# USB_Power.net
KiCad netlist of a schematic drawn in Altium Designer
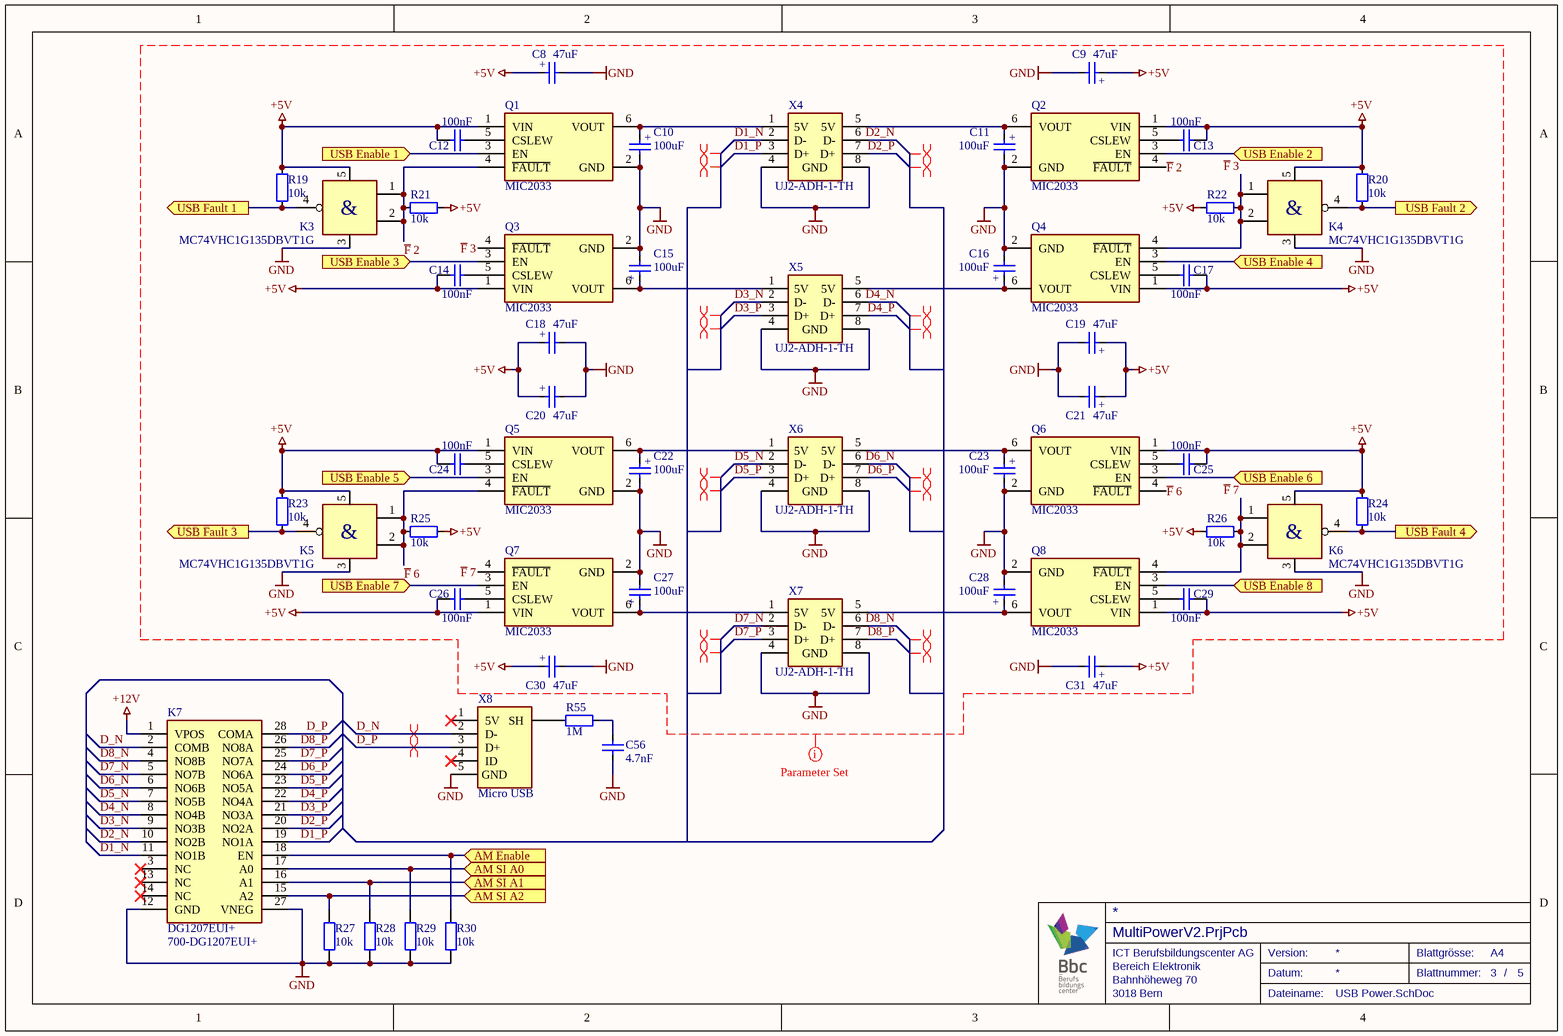
[diagram p0: USB Power.SchDoc]

(export (version "E")
  (design (tool "Eeschema 10.0.6"))
  (components
    (comp (ref "C8")
      (value "47uF")
      (footprint "T58W9476M6R3C0300")
      (description "Polarized Capacitor")
      (fields (field (name "Comment") "Capacitor P") (field (name "PUBLISHER") "ICT Berufsbildungscenter AG"))
      (libsource (lib "SchematicLibrary") (part "Capacitor P"))
    )
    (comp (ref "C9")
      (value "47uF")
      (footprint "T58W9476M6R3C0300")
      (description "Polarized Capacitor")
      (fields (field (name "Comment") "Capacitor P") (field (name "PUBLISHER") "ICT Berufsbildungscenter AG"))
      (libsource (lib "SchematicLibrary") (part "Capacitor P"))
    )
    (comp (ref "C10")
      (value "100uF")
      (footprint "CAP TAN A H")
      (description "Polarized Capacitor")
      (fields (field (name "Comment") "Capacitor P") (field (name "PUBLISHER") "ICT Berufsbildungscenter AG"))
      (libsource (lib "SchematicLibrary") (part "Capacitor P"))
    )
    (comp (ref "C11")
      (value "100uF")
      (footprint "CAP TAN A H")
      (description "Polarized Capacitor")
      (fields (field (name "Comment") "Capacitor P") (field (name "PUBLISHER") "ICT Berufsbildungscenter AG"))
      (libsource (lib "SchematicLibrary") (part "Capacitor P"))
    )
    (comp (ref "C12")
      (value "100nF")
      (footprint "CAP CER 0805 R")
      (description "Non polarized capacitor")
      (fields (field (name "Comment") "Capacitor") (field (name "PUBLISHER") "ICT Berufsbildungscenter AG"))
      (libsource (lib "BBC_Components") (part "Capacitor"))
    )
    (comp (ref "C13")
      (value "100nF")
      (footprint "CAP CER 0805 R")
      (description "Non polarized capacitor")
      (fields (field (name "Comment") "Capacitor") (field (name "PUBLISHER") "ICT Berufsbildungscenter AG"))
      (libsource (lib "BBC_Components") (part "Capacitor"))
    )
    (comp (ref "C14")
      (value "100nF")
      (footprint "CAP CER 0805 R")
      (description "Non polarized capacitor")
      (fields (field (name "Comment") "Capacitor") (field (name "PUBLISHER") "ICT Berufsbildungscenter AG"))
      (libsource (lib "BBC_Components") (part "Capacitor"))
    )
    (comp (ref "C15")
      (value "100uF")
      (footprint "CAP TAN A H")
      (description "Polarized Capacitor")
      (fields (field (name "Comment") "Capacitor P") (field (name "PUBLISHER") "ICT Berufsbildungscenter AG"))
      (libsource (lib "SchematicLibrary") (part "Capacitor P"))
    )
    (comp (ref "C16")
      (value "100uF")
      (footprint "CAP TAN A H")
      (description "Polarized Capacitor")
      (fields (field (name "Comment") "Capacitor P") (field (name "PUBLISHER") "ICT Berufsbildungscenter AG"))
      (libsource (lib "SchematicLibrary") (part "Capacitor P"))
    )
    (comp (ref "C17")
      (value "100nF")
      (footprint "CAP CER 0805 R")
      (description "Non polarized capacitor")
      (fields (field (name "Comment") "Capacitor") (field (name "PUBLISHER") "ICT Berufsbildungscenter AG"))
      (libsource (lib "BBC_Components") (part "Capacitor"))
    )
    (comp (ref "C18")
      (value "47uF")
      (footprint "T58W9476M6R3C0300")
      (description "Polarized Capacitor")
      (fields (field (name "Comment") "Capacitor P") (field (name "PUBLISHER") "ICT Berufsbildungscenter AG"))
      (libsource (lib "SchematicLibrary") (part "Capacitor P"))
    )
    (comp (ref "C19")
      (value "47uF")
      (footprint "T58W9476M6R3C0300")
      (description "Polarized Capacitor")
      (fields (field (name "Comment") "Capacitor P") (field (name "PUBLISHER") "ICT Berufsbildungscenter AG"))
      (libsource (lib "SchematicLibrary") (part "Capacitor P"))
    )
    (comp (ref "C20")
      (value "47uF")
      (footprint "T58W9476M6R3C0300")
      (description "Polarized Capacitor")
      (fields (field (name "Comment") "Capacitor P") (field (name "PUBLISHER") "ICT Berufsbildungscenter AG"))
      (libsource (lib "SchematicLibrary") (part "Capacitor P"))
    )
    (comp (ref "C21")
      (value "47uF")
      (footprint "T58W9476M6R3C0300")
      (description "Polarized Capacitor")
      (fields (field (name "Comment") "Capacitor P") (field (name "PUBLISHER") "ICT Berufsbildungscenter AG"))
      (libsource (lib "SchematicLibrary") (part "Capacitor P"))
    )
    (comp (ref "C22")
      (value "100uF")
      (footprint "CAP TAN A H")
      (description "Polarized Capacitor")
      (fields (field (name "Comment") "Capacitor P") (field (name "PUBLISHER") "ICT Berufsbildungscenter AG"))
      (libsource (lib "SchematicLibrary") (part "Capacitor P"))
    )
    (comp (ref "C23")
      (value "100uF")
      (footprint "CAP TAN A H")
      (description "Polarized Capacitor")
      (fields (field (name "Comment") "Capacitor P") (field (name "PUBLISHER") "ICT Berufsbildungscenter AG"))
      (libsource (lib "SchematicLibrary") (part "Capacitor P"))
    )
    (comp (ref "C24")
      (value "100nF")
      (footprint "CAP CER 0805 R")
      (description "Non polarized capacitor")
      (fields (field (name "Comment") "Capacitor") (field (name "PUBLISHER") "ICT Berufsbildungscenter AG"))
      (libsource (lib "BBC_Components") (part "Capacitor"))
    )
    (comp (ref "C25")
      (value "100nF")
      (footprint "CAP CER 0805 R")
      (description "Non polarized capacitor")
      (fields (field (name "Comment") "Capacitor") (field (name "PUBLISHER") "ICT Berufsbildungscenter AG"))
      (libsource (lib "BBC_Components") (part "Capacitor"))
    )
    (comp (ref "C26")
      (value "100nF")
      (footprint "CAP CER 0805 R")
      (description "Non polarized capacitor")
      (fields (field (name "Comment") "Capacitor") (field (name "PUBLISHER") "ICT Berufsbildungscenter AG"))
      (libsource (lib "BBC_Components") (part "Capacitor"))
    )
    (comp (ref "C27")
      (value "100uF")
      (footprint "CAP TAN A H")
      (description "Polarized Capacitor")
      (fields (field (name "Comment") "Capacitor P") (field (name "PUBLISHER") "ICT Berufsbildungscenter AG"))
      (libsource (lib "SchematicLibrary") (part "Capacitor P"))
    )
    (comp (ref "C28")
      (value "100uF")
      (footprint "CAP TAN A H")
      (description "Polarized Capacitor")
      (fields (field (name "Comment") "Capacitor P") (field (name "PUBLISHER") "ICT Berufsbildungscenter AG"))
      (libsource (lib "SchematicLibrary") (part "Capacitor P"))
    )
    (comp (ref "C29")
      (value "100nF")
      (footprint "CAP CER 0805 R")
      (description "Non polarized capacitor")
      (fields (field (name "Comment") "Capacitor") (field (name "PUBLISHER") "ICT Berufsbildungscenter AG"))
      (libsource (lib "BBC_Components") (part "Capacitor"))
    )
    (comp (ref "C30")
      (value "47uF")
      (footprint "T58W9476M6R3C0300")
      (description "Polarized Capacitor")
      (fields (field (name "Comment") "Capacitor P") (field (name "PUBLISHER") "ICT Berufsbildungscenter AG"))
      (libsource (lib "SchematicLibrary") (part "Capacitor P"))
    )
    (comp (ref "C31")
      (value "47uF")
      (footprint "T58W9476M6R3C0300")
      (description "Polarized Capacitor")
      (fields (field (name "Comment") "Capacitor P") (field (name "PUBLISHER") "ICT Berufsbildungscenter AG"))
      (libsource (lib "SchematicLibrary") (part "Capacitor P"))
    )
    (comp (ref "C56")
      (value "4.7nF")
      (footprint "CAP CER 0805 R")
      (description "Non polarized capacitor")
      (fields (field (name "Comment") "Capacitor") (field (name "PUBLISHER") "ICT Berufsbildungscenter AG"))
      (libsource (lib "SchematicLibrary") (part "Capacitor"))
    )
    (comp (ref "K3")
      (value "MC74VHC1G135DBVT1G")
      (footprint "SOT95P275X110-5N")
      (libsource (lib "") (part "MC74VHC1G135DBVT1G_1"))
    )
    (comp (ref "K4")
      (value "MC74VHC1G135DBVT1G")
      (footprint "SOT95P275X110-5N")
      (libsource (lib "SchematicLibrary") (part "MC74VHC1G135DBVT1G"))
    )
    (comp (ref "K5")
      (value "MC74VHC1G135DBVT1G")
      (footprint "SOT95P275X110-5N")
      (libsource (lib "") (part "MC74VHC1G135DBVT1G_1"))
    )
    (comp (ref "K6")
      (value "MC74VHC1G135DBVT1G")
      (footprint "SOT95P275X110-5N")
      (libsource (lib "SchematicLibrary") (part "MC74VHC1G135DBVT1G"))
    )
    (comp (ref "K7")
      (value "DG1207EUI+")
      (footprint "TSOP65P640X100-28N")
      (description "Analog Switch ICs")
      (fields
        (field (name "MOUSER PART NUMBER") "700-DG1207EUI+")
        (field (name "SUPPLIER PART NUMBER 1") "700-DG1207EUI+")
      )
      (libsource (lib "SchematicLibrary") (part "DG1207EUI+"))
    )
    (comp (ref "Q1")
      (value "MIC2033")
      (footprint "SOT-23-6L")
      (libsource (lib "SchematicLibrary") (part "MIC2033"))
    )
    (comp (ref "Q2") (value "MIC2033") (footprint "SOT-23-6L") (libsource (lib "") (part "MIC2033_3")))
    (comp (ref "Q3") (value "MIC2033") (footprint "SOT-23-6L") (libsource (lib "") (part "MIC2033_1")))
    (comp (ref "Q4") (value "MIC2033") (footprint "SOT-23-6L") (libsource (lib "") (part "MIC2033_2")))
    (comp (ref "Q5")
      (value "MIC2033")
      (footprint "SOT-23-6L")
      (libsource (lib "SchematicLibrary") (part "MIC2033"))
    )
    (comp (ref "Q6") (value "MIC2033") (footprint "SOT-23-6L") (libsource (lib "") (part "MIC2033_3")))
    (comp (ref "Q7") (value "MIC2033") (footprint "SOT-23-6L") (libsource (lib "") (part "MIC2033_1")))
    (comp (ref "Q8") (value "MIC2033") (footprint "SOT-23-6L") (libsource (lib "") (part "MIC2033_2")))
    (comp (ref "R19")
      (value "10k")
      (footprint "RES 0805 R")
      (description "Resistor")
      (fields (field (name "PUBLISHER") "ICT Berufsbildungscenter AG"))
      (libsource (lib "SchematicLibrary") (part "Resistor"))
    )
    (comp (ref "R20")
      (value "10k")
      (footprint "RES 0805 R")
      (description "Resistor")
      (fields (field (name "PUBLISHER") "ICT Berufsbildungscenter AG"))
      (libsource (lib "") (part "Resistor_2"))
    )
    (comp (ref "R21")
      (value "10k")
      (footprint "RES 0805 R")
      (description "Resistor")
      (fields (field (name "PUBLISHER") "ICT Berufsbildungscenter AG"))
      (libsource (lib "") (part "Resistor_2"))
    )
    (comp (ref "R22")
      (value "10k")
      (footprint "RES 0805 R")
      (description "Resistor")
      (fields (field (name "PUBLISHER") "ICT Berufsbildungscenter AG"))
      (libsource (lib "") (part "Resistor_1"))
    )
    (comp (ref "R23")
      (value "10k")
      (footprint "RES 0805 R")
      (description "Resistor")
      (fields (field (name "PUBLISHER") "ICT Berufsbildungscenter AG"))
      (libsource (lib "SchematicLibrary") (part "Resistor"))
    )
    (comp (ref "R24")
      (value "10k")
      (footprint "RES 0805 R")
      (description "Resistor")
      (fields (field (name "PUBLISHER") "ICT Berufsbildungscenter AG"))
      (libsource (lib "") (part "Resistor_2"))
    )
    (comp (ref "R25")
      (value "10k")
      (footprint "RES 0805 R")
      (description "Resistor")
      (fields (field (name "PUBLISHER") "ICT Berufsbildungscenter AG"))
      (libsource (lib "") (part "Resistor_2"))
    )
    (comp (ref "R26")
      (value "10k")
      (footprint "RES 0805 R")
      (description "Resistor")
      (fields (field (name "PUBLISHER") "ICT Berufsbildungscenter AG"))
      (libsource (lib "") (part "Resistor_1"))
    )
    (comp (ref "R27")
      (value "10k")
      (footprint "RES 0805 R")
      (description "Resistor")
      (fields (field (name "PUBLISHER") "ICT Berufsbildungscenter AG"))
      (libsource (lib "BBC_Components") (part "Resistor"))
    )
    (comp (ref "R28")
      (value "10k")
      (footprint "RES 0805 R")
      (description "Resistor")
      (fields (field (name "PUBLISHER") "ICT Berufsbildungscenter AG"))
      (libsource (lib "BBC_Components") (part "Resistor"))
    )
    (comp (ref "R29")
      (value "10k")
      (footprint "RES 0805 R")
      (description "Resistor")
      (fields (field (name "PUBLISHER") "ICT Berufsbildungscenter AG"))
      (libsource (lib "BBC_Components") (part "Resistor"))
    )
    (comp (ref "R30")
      (value "10k")
      (footprint "RES 0805 R")
      (description "Resistor")
      (fields (field (name "PUBLISHER") "ICT Berufsbildungscenter AG"))
      (libsource (lib "BBC_Components") (part "Resistor"))
    )
    (comp (ref "R55")
      (value "1M")
      (footprint "RES 0805 R")
      (description "Resistor")
      (fields (field (name "PUBLISHER") "ICT Berufsbildungscenter AG"))
      (libsource (lib "") (part "Resistor_2"))
    )
    (comp (ref "X4")
      (value "UJ2-ADH-1-TH")
      (footprint "SamacSys:UJ2-ADH-1-TH")
      (description "USB Type A")
      (fields (field (name "MOUSER PART NUMBER") "490-UJ2-ADH-1-TH"))
      (libsource (lib "SchematicLibrary") (part "UJ2-ADH-1-TH"))
    )
    (comp (ref "X5")
      (value "UJ2-ADH-1-TH")
      (footprint "UJ2-ADH-1-TH")
      (description "USB Type A")
      (fields (field (name "MOUSER PART NUMBER") "490-UJ2-ADH-1-TH"))
      (libsource (lib "SchematicLibrary") (part "UJ2-ADH-1-TH"))
    )
    (comp (ref "X6")
      (value "UJ2-ADH-1-TH")
      (footprint "UJ2-ADH-1-TH")
      (description "USB Type A")
      (fields (field (name "MOUSER PART NUMBER") "490-UJ2-ADH-1-TH"))
      (libsource (lib "SchematicLibrary") (part "UJ2-ADH-1-TH"))
    )
    (comp (ref "X7")
      (value "UJ2-ADH-1-TH")
      (footprint "SamacSys:UJ2-ADH-1-TH")
      (description "USB Type A")
      (fields (field (name "MOUSER PART NUMBER") "490-UJ2-ADH-1-TH"))
      (libsource (lib "SchematicLibrary") (part "UJ2-ADH-1-TH"))
    )
    (comp (ref "X8")
      (value "Micro USB")
      (footprint "UJ2-MIBH-4-SMT-TR")
      (description "board to board header")
      (fields (field (name "PUBLISHER") "ICT Berufsbildungscenter AG"))
      (libsource (lib "SchematicLibrary") (part "Micro USB"))
    )
  )
  (nets
    (net (code "1") (name "+5V") (class "Default")
      (node (ref "C12") (pin "1") (pinfunction "1_1") (pintype "passive"))
      (node (ref "C13") (pin "1") (pinfunction "1_1") (pintype "passive"))
      (node (ref "C14") (pin "1") (pinfunction "1_1") (pintype "passive"))
      (node (ref "C17") (pin "1") (pinfunction "1_1") (pintype "passive"))
      (node (ref "C18") (pin "A") (pinfunction "Anode_A") (pintype "passive"))
      (node (ref "C19") (pin "A") (pinfunction "Anode_A") (pintype "passive"))
      (node (ref "C20") (pin "A") (pinfunction "Anode_A") (pintype "passive"))
      (node (ref "C21") (pin "A") (pinfunction "Anode_A") (pintype "passive"))
      (node (ref "C24") (pin "1") (pinfunction "1_1") (pintype "passive"))
      (node (ref "C25") (pin "1") (pinfunction "1_1") (pintype "passive"))
      (node (ref "C26") (pin "1") (pinfunction "1_1") (pintype "passive"))
      (node (ref "C29") (pin "1") (pinfunction "1_1") (pintype "passive"))
      (node (ref "C30") (pin "A") (pinfunction "Anode_A") (pintype "passive"))
      (node (ref "C31") (pin "A") (pinfunction "Anode_A") (pintype "passive"))
      (node (ref "C8") (pin "A") (pinfunction "Anode_A") (pintype "passive"))
      (node (ref "C9") (pin "A") (pinfunction "Anode_A") (pintype "passive"))
      (node (ref "K3") (pin "5") (pinfunction "VCC_5") (pintype "passive"))
      (node (ref "K4") (pin "5") (pinfunction "VCC_5") (pintype "passive"))
      (node (ref "K5") (pin "5") (pinfunction "VCC_5") (pintype "passive"))
      (node (ref "K6") (pin "5") (pinfunction "VCC_5") (pintype "passive"))
      (node (ref "Q1") (pin "1") (pinfunction "VIN_1") (pintype "passive"))
      (node (ref "Q2") (pin "1") (pinfunction "VIN_1") (pintype "passive"))
      (node (ref "Q3") (pin "1") (pinfunction "VIN_1") (pintype "passive"))
      (node (ref "Q4") (pin "1") (pinfunction "VIN_1") (pintype "passive"))
      (node (ref "Q5") (pin "1") (pinfunction "VIN_1") (pintype "passive"))
      (node (ref "Q6") (pin "1") (pinfunction "VIN_1") (pintype "passive"))
      (node (ref "Q7") (pin "1") (pinfunction "VIN_1") (pintype "passive"))
      (node (ref "Q8") (pin "1") (pinfunction "VIN_1") (pintype "passive"))
      (node (ref "R19") (pin "1") (pinfunction "1_1") (pintype "passive"))
      (node (ref "R20") (pin "1") (pinfunction "1_1") (pintype "passive"))
      (node (ref "R21") (pin "1") (pinfunction "1_1") (pintype "passive"))
      (node (ref "R22") (pin "1") (pinfunction "1_1") (pintype "passive"))
      (node (ref "R23") (pin "1") (pinfunction "1_1") (pintype "passive"))
      (node (ref "R24") (pin "1") (pinfunction "1_1") (pintype "passive"))
      (node (ref "R25") (pin "1") (pinfunction "1_1") (pintype "passive"))
      (node (ref "R26") (pin "1") (pinfunction "1_1") (pintype "passive"))
    )
    (net (code "2") (name "+12V") (class "Default")
      (node (ref "K7") (pin "1") (pinfunction "VPOS_1") (pintype "passive"))
    )
    (net (code "3") (name "/AM Enable") (class "Default")
      (node (ref "K7") (pin "18") (pinfunction "EN_18") (pintype "passive"))
      (node (ref "R30") (pin "2") (pinfunction "2_2") (pintype "passive"))
    )
    (net (code "4") (name "/AM SI A0") (class "Default")
      (node (ref "K7") (pin "17") (pinfunction "A0_17") (pintype "passive"))
      (node (ref "R29") (pin "2") (pinfunction "2_2") (pintype "passive"))
    )
    (net (code "5") (name "/AM SI A1") (class "Default")
      (node (ref "K7") (pin "16") (pinfunction "A1_16") (pintype "passive"))
      (node (ref "R28") (pin "2") (pinfunction "2_2") (pintype "passive"))
    )
    (net (code "6") (name "/AM SI A2") (class "Default")
      (node (ref "K7") (pin "15") (pinfunction "A2_15") (pintype "passive"))
      (node (ref "R27") (pin "2") (pinfunction "2_2") (pintype "passive"))
    )
    (net (code "7") (name "/D1_N") (class "Default")
      (node (ref "K7") (pin "11") (pinfunction "NO1B_11") (pintype "passive"))
      (node (ref "X4") (pin "2") (pinfunction "D-_2") (pintype "passive"))
    )
    (net (code "8") (name "/D1_P") (class "Default")
      (node (ref "K7") (pin "19") (pinfunction "NO1A_19") (pintype "passive"))
      (node (ref "X4") (pin "3") (pinfunction "D+_3") (pintype "passive"))
    )
    (net (code "9") (name "/D2_N") (class "Default")
      (node (ref "K7") (pin "10") (pinfunction "NO2B_10") (pintype "passive"))
      (node (ref "X4") (pin "6") (pinfunction "D-_6") (pintype "passive"))
    )
    (net (code "10") (name "/D2_P") (class "Default")
      (node (ref "K7") (pin "20") (pinfunction "NO2A_20") (pintype "passive"))
      (node (ref "X4") (pin "7") (pinfunction "D+_7") (pintype "passive"))
    )
    (net (code "11") (name "/D3_N") (class "Default")
      (node (ref "K7") (pin "9") (pinfunction "NO3B_9") (pintype "passive"))
      (node (ref "X5") (pin "2") (pinfunction "D-_2") (pintype "passive"))
    )
    (net (code "12") (name "/D3_P") (class "Default")
      (node (ref "K7") (pin "21") (pinfunction "NO3A_21") (pintype "passive"))
      (node (ref "X5") (pin "3") (pinfunction "D+_3") (pintype "passive"))
    )
    (net (code "13") (name "/D4_N") (class "Default")
      (node (ref "K7") (pin "8") (pinfunction "NO4B_8") (pintype "passive"))
      (node (ref "X5") (pin "6") (pinfunction "D-_6") (pintype "passive"))
    )
    (net (code "14") (name "/D4_P") (class "Default")
      (node (ref "K7") (pin "22") (pinfunction "NO4A_22") (pintype "passive"))
      (node (ref "X5") (pin "7") (pinfunction "D+_7") (pintype "passive"))
    )
    (net (code "15") (name "/D5_N") (class "Default")
      (node (ref "K7") (pin "7") (pinfunction "NO5B_7") (pintype "passive"))
      (node (ref "X6") (pin "2") (pinfunction "D-_2") (pintype "passive"))
    )
    (net (code "16") (name "/D5_P") (class "Default")
      (node (ref "K7") (pin "23") (pinfunction "NO5A_23") (pintype "passive"))
      (node (ref "X6") (pin "3") (pinfunction "D+_3") (pintype "passive"))
    )
    (net (code "17") (name "/D6_N") (class "Default")
      (node (ref "K7") (pin "6") (pinfunction "NO6B_6") (pintype "passive"))
      (node (ref "X6") (pin "6") (pinfunction "D-_6") (pintype "passive"))
    )
    (net (code "18") (name "/D6_P") (class "Default")
      (node (ref "K7") (pin "24") (pinfunction "NO6A_24") (pintype "passive"))
      (node (ref "X6") (pin "7") (pinfunction "D+_7") (pintype "passive"))
    )
    (net (code "19") (name "/D7_N") (class "Default")
      (node (ref "K7") (pin "5") (pinfunction "NO7B_5") (pintype "passive"))
      (node (ref "X7") (pin "2") (pinfunction "D-_2") (pintype "passive"))
    )
    (net (code "20") (name "/D7_P") (class "Default")
      (node (ref "K7") (pin "25") (pinfunction "NO7A_25") (pintype "passive"))
      (node (ref "X7") (pin "3") (pinfunction "D+_3") (pintype "passive"))
    )
    (net (code "21") (name "/D8_N") (class "Default")
      (node (ref "K7") (pin "4") (pinfunction "NO8B_4") (pintype "passive"))
      (node (ref "X7") (pin "6") (pinfunction "D-_6") (pintype "passive"))
    )
    (net (code "22") (name "/D8_P") (class "Default")
      (node (ref "K7") (pin "26") (pinfunction "NO8A_26") (pintype "passive"))
      (node (ref "X7") (pin "7") (pinfunction "D+_7") (pintype "passive"))
    )
    (net (code "23") (name "/D_N") (class "Default")
      (node (ref "K7") (pin "2") (pinfunction "COMB_2") (pintype "passive"))
      (node (ref "X8") (pin "2") (pinfunction "D-_2") (pintype "passive"))
    )
    (net (code "24") (name "/D_P") (class "Default")
      (node (ref "K7") (pin "28") (pinfunction "COMA_28") (pintype "passive"))
      (node (ref "X8") (pin "3") (pinfunction "D+_3") (pintype "passive"))
    )
    (net (code "25") (name "/USB Enable 1") (class "Default")
      (node (ref "Q1") (pin "3") (pinfunction "EN_3") (pintype "passive"))
    )
    (net (code "26") (name "/USB Enable 2") (class "Default")
      (node (ref "Q2") (pin "3") (pinfunction "EN_3") (pintype "passive"))
    )
    (net (code "27") (name "/USB Enable 3") (class "Default")
      (node (ref "Q3") (pin "3") (pinfunction "EN_3") (pintype "passive"))
    )
    (net (code "28") (name "/USB Enable 4") (class "Default")
      (node (ref "Q4") (pin "3") (pinfunction "EN_3") (pintype "passive"))
    )
    (net (code "29") (name "/USB Enable 5") (class "Default")
      (node (ref "Q5") (pin "3") (pinfunction "EN_3") (pintype "passive"))
    )
    (net (code "30") (name "/USB Enable 6") (class "Default")
      (node (ref "Q6") (pin "3") (pinfunction "EN_3") (pintype "passive"))
    )
    (net (code "31") (name "/USB Enable 7") (class "Default")
      (node (ref "Q7") (pin "3") (pinfunction "EN_3") (pintype "passive"))
    )
    (net (code "32") (name "/USB Enable 8") (class "Default")
      (node (ref "Q8") (pin "3") (pinfunction "EN_3") (pintype "passive"))
    )
    (net (code "33") (name "/USB Fault 1") (class "Default")
      (node (ref "K3") (pin "4") (pinfunction "Y_4") (pintype "passive"))
      (node (ref "R19") (pin "2") (pinfunction "2_2") (pintype "passive"))
    )
    (net (code "34") (name "/USB Fault 2") (class "Default")
      (node (ref "K4") (pin "4") (pinfunction "Y_4") (pintype "passive"))
      (node (ref "R20") (pin "2") (pinfunction "2_2") (pintype "passive"))
    )
    (net (code "35") (name "/USB Fault 3") (class "Default")
      (node (ref "K5") (pin "4") (pinfunction "Y_4") (pintype "passive"))
      (node (ref "R23") (pin "2") (pinfunction "2_2") (pintype "passive"))
    )
    (net (code "36") (name "/USB Fault 4") (class "Default")
      (node (ref "K6") (pin "4") (pinfunction "Y_4") (pintype "passive"))
      (node (ref "R24") (pin "2") (pinfunction "2_2") (pintype "passive"))
    )
    (net (code "37") (name "/~{F} 2") (class "Default")
      (node (ref "K3") (pin "1") (pinfunction "A_1") (pintype "passive"))
      (node (ref "K3") (pin "2") (pinfunction "B_2") (pintype "passive"))
      (node (ref "Q1") (pin "4") (pinfunction "~{FAULT}_4") (pintype "passive"))
      (node (ref "Q2") (pin "4") (pinfunction "~{FAULT}_4") (pintype "passive"))
      (node (ref "R21") (pin "2") (pinfunction "2_2") (pintype "passive"))
    )
    (net (code "38") (name "/~{F} 3") (class "Default")
      (node (ref "K4") (pin "1") (pinfunction "A_1") (pintype "passive"))
      (node (ref "K4") (pin "2") (pinfunction "B_2") (pintype "passive"))
      (node (ref "Q3") (pin "4") (pinfunction "~{FAULT}_4") (pintype "passive"))
      (node (ref "Q4") (pin "4") (pinfunction "~{FAULT}_4") (pintype "passive"))
      (node (ref "R22") (pin "2") (pinfunction "2_2") (pintype "passive"))
    )
    (net (code "39") (name "/~{F} 6") (class "Default")
      (node (ref "K5") (pin "1") (pinfunction "A_1") (pintype "passive"))
      (node (ref "K5") (pin "2") (pinfunction "B_2") (pintype "passive"))
      (node (ref "Q5") (pin "4") (pinfunction "~{FAULT}_4") (pintype "passive"))
      (node (ref "Q6") (pin "4") (pinfunction "~{FAULT}_4") (pintype "passive"))
      (node (ref "R25") (pin "2") (pinfunction "2_2") (pintype "passive"))
    )
    (net (code "40") (name "/~{F} 7") (class "Default")
      (node (ref "K6") (pin "1") (pinfunction "A_1") (pintype "passive"))
      (node (ref "K6") (pin "2") (pinfunction "B_2") (pintype "passive"))
      (node (ref "Q7") (pin "4") (pinfunction "~{FAULT}_4") (pintype "passive"))
      (node (ref "Q8") (pin "4") (pinfunction "~{FAULT}_4") (pintype "passive"))
      (node (ref "R26") (pin "2") (pinfunction "2_2") (pintype "passive"))
    )
    (net (code "41") (name "GND") (class "Default")
      (node (ref "C10") (pin "C") (pinfunction "Cathode_C") (pintype "passive"))
      (node (ref "C11") (pin "C") (pinfunction "Cathode_C") (pintype "passive"))
      (node (ref "C15") (pin "C") (pinfunction "Cathode_C") (pintype "passive"))
      (node (ref "C16") (pin "C") (pinfunction "Cathode_C") (pintype "passive"))
      (node (ref "C18") (pin "C") (pinfunction "Cathode_C") (pintype "passive"))
      (node (ref "C19") (pin "C") (pinfunction "Cathode_C") (pintype "passive"))
      (node (ref "C20") (pin "C") (pinfunction "Cathode_C") (pintype "passive"))
      (node (ref "C21") (pin "C") (pinfunction "Cathode_C") (pintype "passive"))
      (node (ref "C22") (pin "C") (pinfunction "Cathode_C") (pintype "passive"))
      (node (ref "C23") (pin "C") (pinfunction "Cathode_C") (pintype "passive"))
      (node (ref "C27") (pin "C") (pinfunction "Cathode_C") (pintype "passive"))
      (node (ref "C28") (pin "C") (pinfunction "Cathode_C") (pintype "passive"))
      (node (ref "C30") (pin "C") (pinfunction "Cathode_C") (pintype "passive"))
      (node (ref "C31") (pin "C") (pinfunction "Cathode_C") (pintype "passive"))
      (node (ref "C56") (pin "1") (pinfunction "1_1") (pintype "passive"))
      (node (ref "C8") (pin "C") (pinfunction "Cathode_C") (pintype "passive"))
      (node (ref "C9") (pin "C") (pinfunction "Cathode_C") (pintype "passive"))
      (node (ref "K3") (pin "3") (pinfunction "GND_3") (pintype "passive"))
      (node (ref "K4") (pin "3") (pinfunction "GND_3") (pintype "passive"))
      (node (ref "K5") (pin "3") (pinfunction "GND_3") (pintype "passive"))
      (node (ref "K6") (pin "3") (pinfunction "GND_3") (pintype "passive"))
      (node (ref "K7") (pin "12") (pinfunction "GND_12") (pintype "passive"))
      (node (ref "K7") (pin "27") (pinfunction "VNEG_27") (pintype "passive"))
      (node (ref "Q1") (pin "2") (pinfunction "GND_2") (pintype "passive"))
      (node (ref "Q2") (pin "2") (pinfunction "GND_2") (pintype "passive"))
      (node (ref "Q3") (pin "2") (pinfunction "GND_2") (pintype "passive"))
      (node (ref "Q4") (pin "2") (pinfunction "GND_2") (pintype "passive"))
      (node (ref "Q5") (pin "2") (pinfunction "GND_2") (pintype "passive"))
      (node (ref "Q6") (pin "2") (pinfunction "GND_2") (pintype "passive"))
      (node (ref "Q7") (pin "2") (pinfunction "GND_2") (pintype "passive"))
      (node (ref "Q8") (pin "2") (pinfunction "GND_2") (pintype "passive"))
      (node (ref "R27") (pin "1") (pinfunction "1_1") (pintype "passive"))
      (node (ref "R28") (pin "1") (pinfunction "1_1") (pintype "passive"))
      (node (ref "R29") (pin "1") (pinfunction "1_1") (pintype "passive"))
      (node (ref "R30") (pin "1") (pinfunction "1_1") (pintype "passive"))
      (node (ref "X4") (pin "4") (pinfunction "GND_4") (pintype "passive"))
      (node (ref "X4") (pin "8") (pinfunction "GND_8") (pintype "passive"))
      (node (ref "X5") (pin "4") (pinfunction "GND_4") (pintype "passive"))
      (node (ref "X5") (pin "8") (pinfunction "GND_8") (pintype "passive"))
      (node (ref "X6") (pin "4") (pinfunction "GND_4") (pintype "passive"))
      (node (ref "X6") (pin "8") (pinfunction "GND_8") (pintype "passive"))
      (node (ref "X7") (pin "4") (pinfunction "GND_4") (pintype "passive"))
      (node (ref "X7") (pin "8") (pinfunction "GND_8") (pintype "passive"))
      (node (ref "X8") (pin "5") (pinfunction "GND_5") (pintype "passive"))
    )
    (net (code "42") (name "Net-(C10-Anode)") (class "Default")
      (node (ref "C10") (pin "A") (pinfunction "Anode_A") (pintype "passive"))
      (node (ref "Q1") (pin "6") (pinfunction "VOUT_6") (pintype "passive"))
      (node (ref "X4") (pin "1") (pinfunction "5V_1") (pintype "passive"))
    )
    (net (code "43") (name "Net-(C11-Anode)") (class "Default")
      (node (ref "C11") (pin "A") (pinfunction "Anode_A") (pintype "passive"))
      (node (ref "Q2") (pin "6") (pinfunction "VOUT_6") (pintype "passive"))
      (node (ref "X4") (pin "5") (pinfunction "5V_5") (pintype "passive"))
    )
    (net (code "44") (name "Net-(C15-Anode)") (class "Default")
      (node (ref "C15") (pin "A") (pinfunction "Anode_A") (pintype "passive"))
      (node (ref "Q3") (pin "6") (pinfunction "VOUT_6") (pintype "passive"))
      (node (ref "X5") (pin "1") (pinfunction "5V_1") (pintype "passive"))
    )
    (net (code "45") (name "Net-(C16-Anode)") (class "Default")
      (node (ref "C16") (pin "A") (pinfunction "Anode_A") (pintype "passive"))
      (node (ref "Q4") (pin "6") (pinfunction "VOUT_6") (pintype "passive"))
      (node (ref "X5") (pin "5") (pinfunction "5V_5") (pintype "passive"))
    )
    (net (code "46") (name "Net-(C22-Anode)") (class "Default")
      (node (ref "C22") (pin "A") (pinfunction "Anode_A") (pintype "passive"))
      (node (ref "Q5") (pin "6") (pinfunction "VOUT_6") (pintype "passive"))
      (node (ref "X6") (pin "1") (pinfunction "5V_1") (pintype "passive"))
    )
    (net (code "47") (name "Net-(C23-Anode)") (class "Default")
      (node (ref "C23") (pin "A") (pinfunction "Anode_A") (pintype "passive"))
      (node (ref "Q6") (pin "6") (pinfunction "VOUT_6") (pintype "passive"))
      (node (ref "X6") (pin "5") (pinfunction "5V_5") (pintype "passive"))
    )
    (net (code "48") (name "Net-(C27-Anode)") (class "Default")
      (node (ref "C27") (pin "A") (pinfunction "Anode_A") (pintype "passive"))
      (node (ref "Q7") (pin "6") (pinfunction "VOUT_6") (pintype "passive"))
      (node (ref "X7") (pin "1") (pinfunction "5V_1") (pintype "passive"))
    )
    (net (code "49") (name "Net-(C28-Anode)") (class "Default")
      (node (ref "C28") (pin "A") (pinfunction "Anode_A") (pintype "passive"))
      (node (ref "Q8") (pin "6") (pinfunction "VOUT_6") (pintype "passive"))
      (node (ref "X7") (pin "5") (pinfunction "5V_5") (pintype "passive"))
    )
    (net (code "50") (name "Net-(C56-Pad2)") (class "Default")
      (node (ref "C56") (pin "2") (pinfunction "2_2") (pintype "passive"))
      (node (ref "R55") (pin "1") (pinfunction "1_1") (pintype "passive"))
    )
    (net (code "51") (name "Net-(Q1-CSLEW)") (class "Default")
      (node (ref "C12") (pin "2") (pinfunction "2_2") (pintype "passive"))
      (node (ref "Q1") (pin "5") (pinfunction "CSLEW_5") (pintype "passive"))
    )
    (net (code "52") (name "Net-(Q2-CSLEW)") (class "Default")
      (node (ref "C13") (pin "2") (pinfunction "2_2") (pintype "passive"))
      (node (ref "Q2") (pin "5") (pinfunction "CSLEW_5") (pintype "passive"))
    )
    (net (code "53") (name "Net-(Q3-CSLEW)") (class "Default")
      (node (ref "C14") (pin "2") (pinfunction "2_2") (pintype "passive"))
      (node (ref "Q3") (pin "5") (pinfunction "CSLEW_5") (pintype "passive"))
    )
    (net (code "54") (name "Net-(Q4-CSLEW)") (class "Default")
      (node (ref "C17") (pin "2") (pinfunction "2_2") (pintype "passive"))
      (node (ref "Q4") (pin "5") (pinfunction "CSLEW_5") (pintype "passive"))
    )
    (net (code "55") (name "Net-(Q5-CSLEW)") (class "Default")
      (node (ref "C24") (pin "2") (pinfunction "2_2") (pintype "passive"))
      (node (ref "Q5") (pin "5") (pinfunction "CSLEW_5") (pintype "passive"))
    )
    (net (code "56") (name "Net-(Q6-CSLEW)") (class "Default")
      (node (ref "C25") (pin "2") (pinfunction "2_2") (pintype "passive"))
      (node (ref "Q6") (pin "5") (pinfunction "CSLEW_5") (pintype "passive"))
    )
    (net (code "57") (name "Net-(Q7-CSLEW)") (class "Default")
      (node (ref "C26") (pin "2") (pinfunction "2_2") (pintype "passive"))
      (node (ref "Q7") (pin "5") (pinfunction "CSLEW_5") (pintype "passive"))
    )
    (net (code "58") (name "Net-(Q8-CSLEW)") (class "Default")
      (node (ref "C29") (pin "2") (pinfunction "2_2") (pintype "passive"))
      (node (ref "Q8") (pin "5") (pinfunction "CSLEW_5") (pintype "passive"))
    )
    (net (code "59") (name "Net-(R55-Pad2)") (class "Default")
      (node (ref "R55") (pin "2") (pinfunction "2_2") (pintype "passive"))
      (node (ref "X8") (pin "SH") (pinfunction "SH_SH") (pintype "passive"))
    )
    (net (code "60") (name "unconnected-(K7-NC-Pad3)") (class "Default")
      (node (ref "K7") (pin "3") (pinfunction "NC_3") (pintype "passive+no_connect"))
    )
    (net (code "61") (name "unconnected-(K7-NC-Pad13)") (class "Default")
      (node (ref "K7") (pin "13") (pinfunction "NC_13") (pintype "passive+no_connect"))
    )
    (net (code "62") (name "unconnected-(K7-NC-Pad14)") (class "Default")
      (node (ref "K7") (pin "14") (pinfunction "NC_14") (pintype "passive+no_connect"))
    )
    (net (code "63") (name "unconnected-(X8-5V-Pad1)") (class "Default")
      (node (ref "X8") (pin "1") (pinfunction "5V_1") (pintype "passive+no_connect"))
    )
    (net (code "64") (name "unconnected-(X8-ID-Pad4)") (class "Default")
      (node (ref "X8") (pin "4") (pinfunction "ID_4") (pintype "passive+no_connect"))
    )
  )
)
